# ADC.net
KiCad netlist of a schematic drawn in Altium Designer
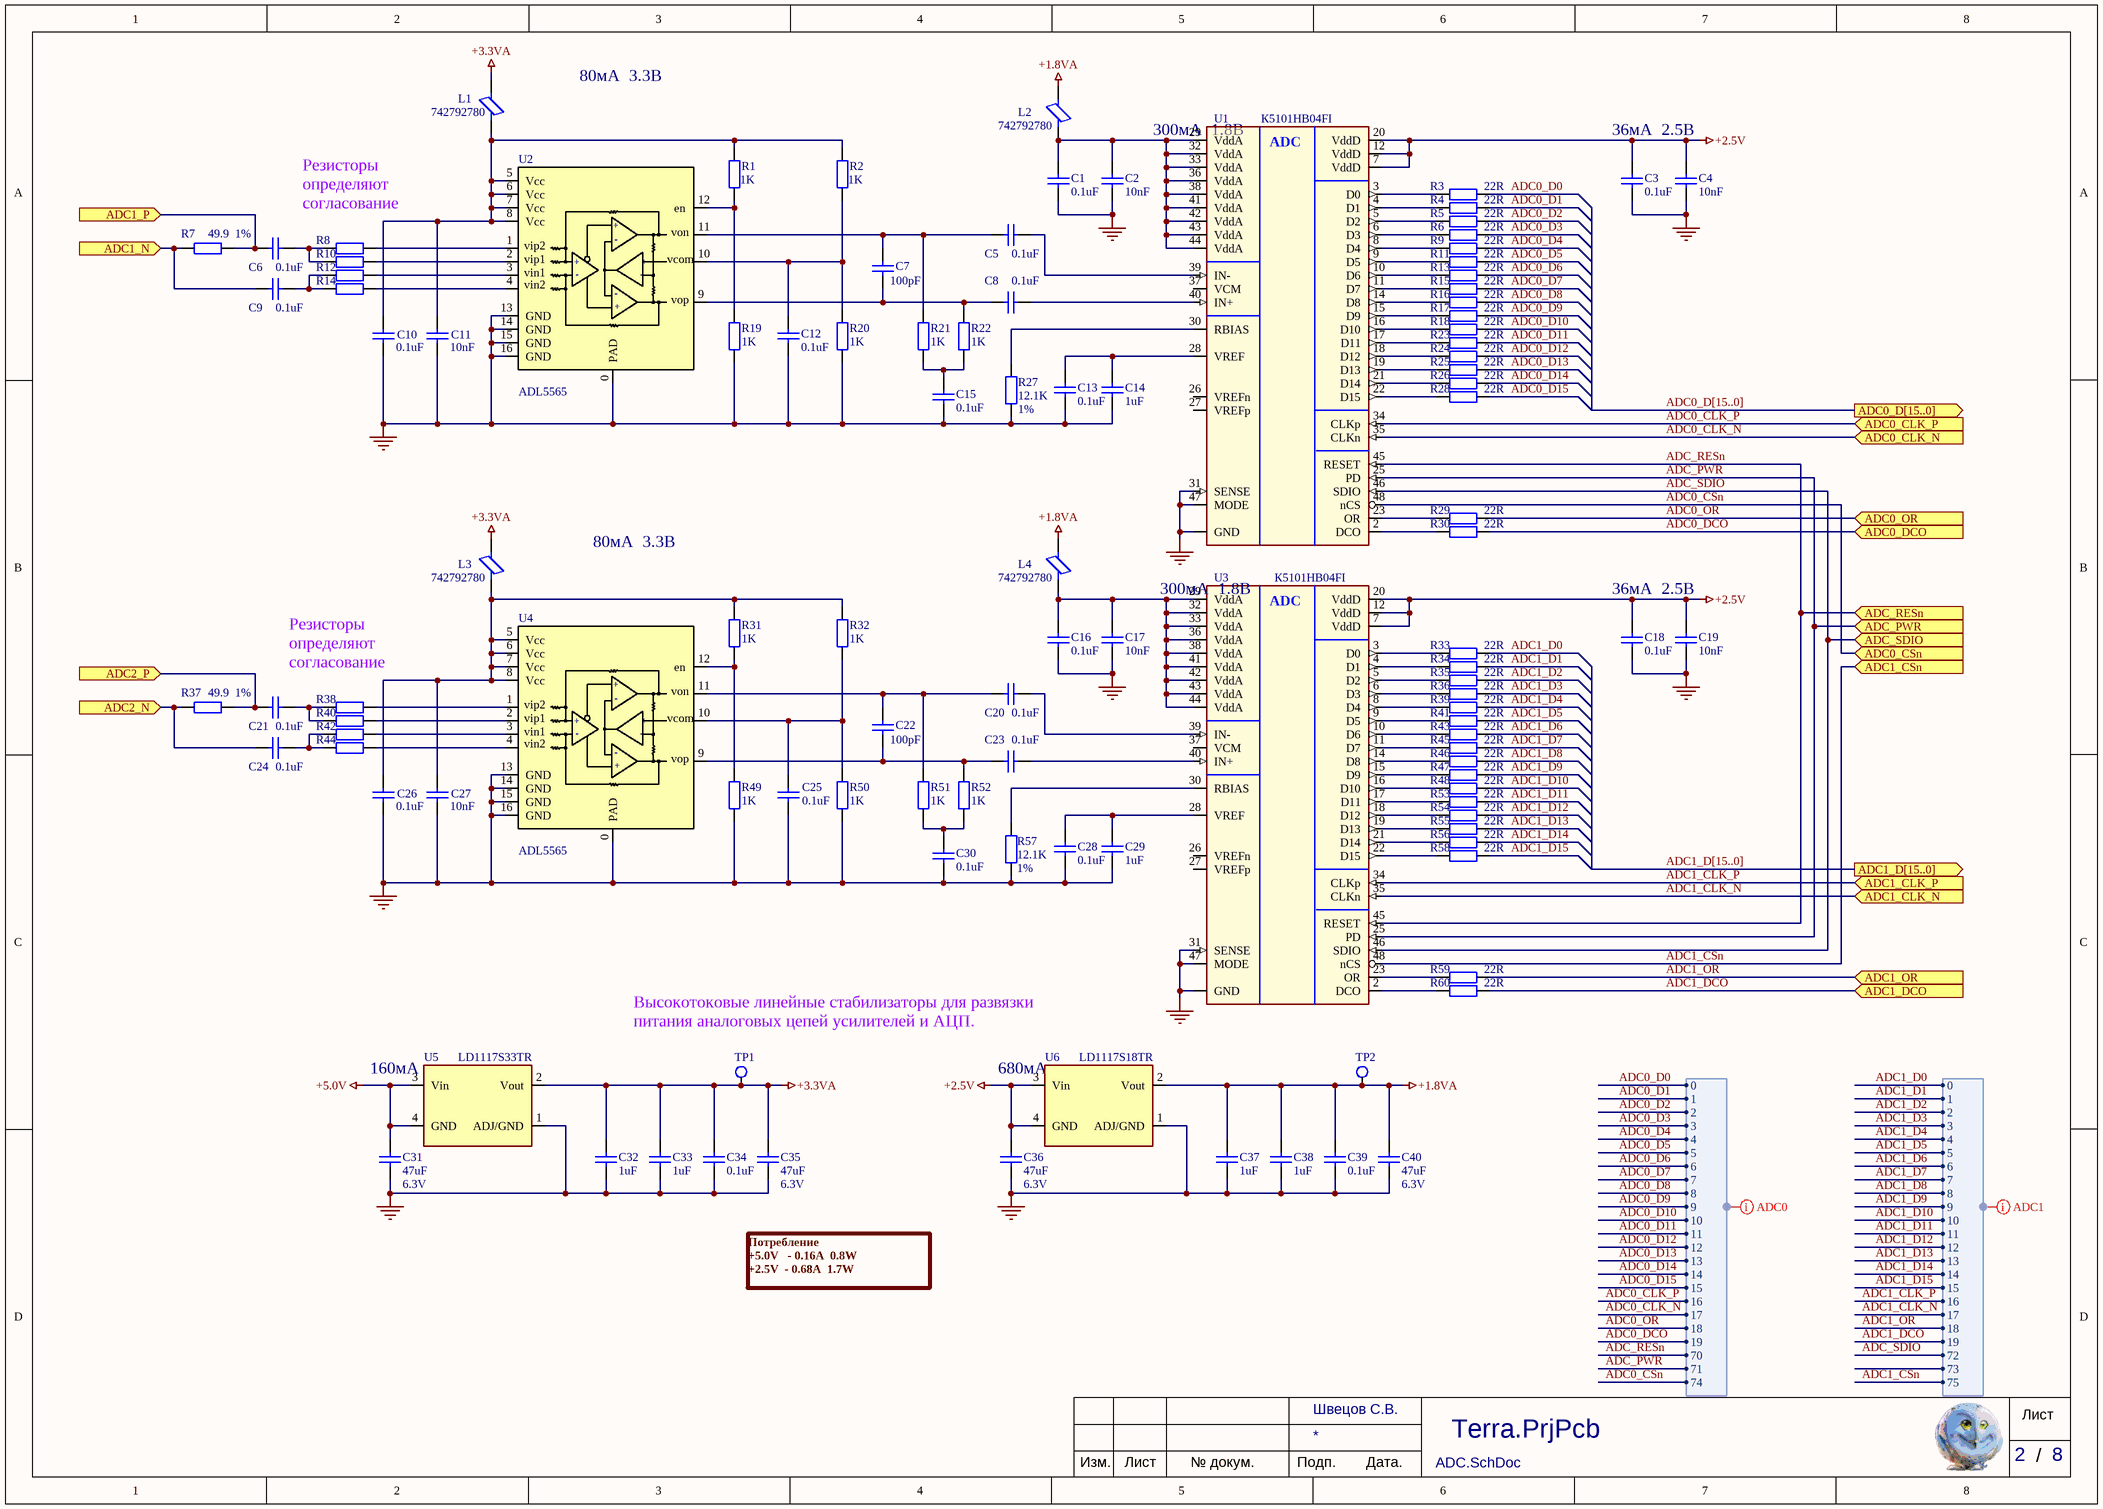
[diagram p0: ADC.SchDoc]

(export (version "E")
  (design (tool "Eeschema 10.0.6"))
  (components
    (comp (ref "C1")
      (value "0.1uF")
      (footprint "C0402")
      (description "Конденсатор керамический")
      (fields (field (name "VOLTAGE") "25V") (field (name "Comment") "Cap"))
      (libsource (lib "Terra") (part "Cap"))
    )
    (comp (ref "C2")
      (value "10nF")
      (footprint "C0402")
      (description "Конденсатор керамический")
      (fields (field (name "VOLTAGE") "25V") (field (name "Comment") "Cap"))
      (libsource (lib "Terra") (part "Cap"))
    )
    (comp (ref "C3")
      (value "0.1uF")
      (footprint "C0402")
      (description "Конденсатор керамический")
      (fields (field (name "VOLTAGE") "25V") (field (name "Comment") "Cap"))
      (libsource (lib "Terra") (part "Cap"))
    )
    (comp (ref "C4")
      (value "10nF")
      (footprint "C0402")
      (description "Конденсатор керамический")
      (fields (field (name "VOLTAGE") "25V") (field (name "Comment") "Cap"))
      (libsource (lib "Terra") (part "Cap"))
    )
    (comp (ref "C5")
      (value "0.1uF")
      (footprint "C0402")
      (description "Конденсатор керамический")
      (fields (field (name "VOLTAGE") "25V") (field (name "Comment") "Cap"))
      (libsource (lib "Terra") (part "Cap"))
    )
    (comp (ref "C6")
      (value "0.1uF")
      (footprint "C0402")
      (description "Конденсатор керамический")
      (fields (field (name "VOLTAGE") "25V") (field (name "Comment") "Cap"))
      (libsource (lib "Terra") (part "Cap"))
    )
    (comp (ref "C7")
      (value "100pF")
      (footprint "C0402")
      (description "Конденсатор керамический")
      (fields (field (name "Comment") "Cap"))
      (libsource (lib "Terra") (part "Cap"))
    )
    (comp (ref "C8")
      (value "0.1uF")
      (footprint "C0402")
      (description "Конденсатор керамический")
      (fields (field (name "VOLTAGE") "25V") (field (name "Comment") "Cap"))
      (libsource (lib "Terra") (part "Cap"))
    )
    (comp (ref "C9")
      (value "0.1uF")
      (footprint "C0402")
      (description "Конденсатор керамический")
      (fields (field (name "VOLTAGE") "25V") (field (name "Comment") "Cap"))
      (libsource (lib "Terra") (part "Cap"))
    )
    (comp (ref "C10")
      (value "0.1uF")
      (footprint "C0402")
      (description "Конденсатор керамический")
      (fields (field (name "VOLTAGE") "25V") (field (name "Comment") "Cap"))
      (libsource (lib "Terra") (part "Cap"))
    )
    (comp (ref "C11")
      (value "10nF")
      (footprint "C0402")
      (description "Конденсатор керамический")
      (fields (field (name "VOLTAGE") "25V") (field (name "Comment") "Cap"))
      (libsource (lib "Terra") (part "Cap"))
    )
    (comp (ref "C12")
      (value "0.1uF")
      (footprint "C0402")
      (description "Конденсатор керамический")
      (fields (field (name "VOLTAGE") "25V") (field (name "Comment") "Cap"))
      (libsource (lib "Terra") (part "Cap"))
    )
    (comp (ref "C13")
      (value "0.1uF")
      (footprint "C0402")
      (description "Конденсатор керамический")
      (fields (field (name "VOLTAGE") "25V") (field (name "Comment") "Cap"))
      (libsource (lib "Terra") (part "Cap"))
    )
    (comp (ref "C14")
      (value "1uF")
      (footprint "C0603")
      (description "Конденсатор керамический")
      (fields (field (name "Comment") "Cap"))
      (libsource (lib "Terra") (part "Cap"))
    )
    (comp (ref "C15")
      (value "0.1uF")
      (footprint "C0402")
      (description "Конденсатор керамический")
      (fields (field (name "VOLTAGE") "25V") (field (name "Comment") "Cap"))
      (libsource (lib "Terra") (part "Cap"))
    )
    (comp (ref "C16")
      (value "0.1uF")
      (footprint "C0402")
      (description "Конденсатор керамический")
      (fields (field (name "VOLTAGE") "25V") (field (name "Comment") "Cap"))
      (libsource (lib "Terra") (part "Cap"))
    )
    (comp (ref "C17")
      (value "10nF")
      (footprint "C0402")
      (description "Конденсатор керамический")
      (fields (field (name "VOLTAGE") "25V") (field (name "Comment") "Cap"))
      (libsource (lib "Terra") (part "Cap"))
    )
    (comp (ref "C18")
      (value "0.1uF")
      (footprint "C0402")
      (description "Конденсатор керамический")
      (fields (field (name "VOLTAGE") "25V") (field (name "Comment") "Cap"))
      (libsource (lib "Terra") (part "Cap"))
    )
    (comp (ref "C19")
      (value "10nF")
      (footprint "C0402")
      (description "Конденсатор керамический")
      (fields (field (name "VOLTAGE") "25V") (field (name "Comment") "Cap"))
      (libsource (lib "Terra") (part "Cap"))
    )
    (comp (ref "C20")
      (value "0.1uF")
      (footprint "C0402")
      (description "Конденсатор керамический")
      (fields (field (name "VOLTAGE") "25V") (field (name "Comment") "Cap"))
      (libsource (lib "Terra") (part "Cap"))
    )
    (comp (ref "C21")
      (value "0.1uF")
      (footprint "C0402")
      (description "Конденсатор керамический")
      (fields (field (name "VOLTAGE") "25V") (field (name "Comment") "Cap"))
      (libsource (lib "Terra") (part "Cap"))
    )
    (comp (ref "C22")
      (value "100pF")
      (footprint "C0402")
      (description "Конденсатор керамический")
      (fields (field (name "Comment") "Cap"))
      (libsource (lib "Terra") (part "Cap"))
    )
    (comp (ref "C23")
      (value "0.1uF")
      (footprint "C0402")
      (description "Конденсатор керамический")
      (fields (field (name "VOLTAGE") "25V") (field (name "Comment") "Cap"))
      (libsource (lib "Terra") (part "Cap"))
    )
    (comp (ref "C24")
      (value "0.1uF")
      (footprint "C0402")
      (description "Конденсатор керамический")
      (fields (field (name "VOLTAGE") "25V") (field (name "Comment") "Cap"))
      (libsource (lib "Terra") (part "Cap"))
    )
    (comp (ref "C25")
      (value "0.1uF")
      (footprint "C0402")
      (description "Конденсатор керамический")
      (fields (field (name "VOLTAGE") "25V") (field (name "Comment") "Cap"))
      (libsource (lib "Terra") (part "Cap"))
    )
    (comp (ref "C26")
      (value "0.1uF")
      (footprint "C0402")
      (description "Конденсатор керамический")
      (fields (field (name "VOLTAGE") "25V") (field (name "Comment") "Cap"))
      (libsource (lib "Terra") (part "Cap"))
    )
    (comp (ref "C27")
      (value "10nF")
      (footprint "C0402")
      (description "Конденсатор керамический")
      (fields (field (name "VOLTAGE") "25V") (field (name "Comment") "Cap"))
      (libsource (lib "Terra") (part "Cap"))
    )
    (comp (ref "C28")
      (value "0.1uF")
      (footprint "C0402")
      (description "Конденсатор керамический")
      (fields (field (name "VOLTAGE") "25V") (field (name "Comment") "Cap"))
      (libsource (lib "Terra") (part "Cap"))
    )
    (comp (ref "C29")
      (value "1uF")
      (footprint "C0603")
      (description "Конденсатор керамический")
      (fields (field (name "Comment") "Cap"))
      (libsource (lib "Terra") (part "Cap"))
    )
    (comp (ref "C30")
      (value "0.1uF")
      (footprint "C0402")
      (description "Конденсатор керамический")
      (fields (field (name "VOLTAGE") "25V") (field (name "Comment") "Cap"))
      (libsource (lib "Terra") (part "Cap"))
    )
    (comp (ref "C31")
      (value "47uF")
      (footprint "C0805")
      (description "C0805C476M9PAC")
      (fields (field (name "VOLTAGE") "6.3V") (field (name "Comment") "Cap"))
      (libsource (lib "Terra") (part "Cap"))
    )
    (comp (ref "C32")
      (value "1uF")
      (footprint "C0603")
      (description "Конденсатор керамический")
      (fields (field (name "Comment") "Cap"))
      (libsource (lib "Terra") (part "Cap"))
    )
    (comp (ref "C33")
      (value "1uF")
      (footprint "C0603")
      (description "Конденсатор керамический")
      (fields (field (name "Comment") "Cap"))
      (libsource (lib "Terra") (part "Cap"))
    )
    (comp (ref "C34")
      (value "0.1uF")
      (footprint "C0402")
      (description "Конденсатор керамический")
      (fields (field (name "VOLTAGE") "25V") (field (name "Comment") "Cap"))
      (libsource (lib "Terra") (part "Cap"))
    )
    (comp (ref "C35")
      (value "47uF")
      (footprint "C0805")
      (description "C0805C476M9PAC")
      (fields (field (name "VOLTAGE") "6.3V") (field (name "Comment") "Cap"))
      (libsource (lib "Terra") (part "Cap"))
    )
    (comp (ref "C36")
      (value "47uF")
      (footprint "C0805")
      (description "C0805C476M9PAC")
      (fields (field (name "VOLTAGE") "6.3V") (field (name "Comment") "Cap"))
      (libsource (lib "Terra") (part "Cap"))
    )
    (comp (ref "C37")
      (value "1uF")
      (footprint "C0603")
      (description "Конденсатор керамический")
      (fields (field (name "Comment") "Cap"))
      (libsource (lib "Terra") (part "Cap"))
    )
    (comp (ref "C38")
      (value "1uF")
      (footprint "C0603")
      (description "Конденсатор керамический")
      (fields (field (name "Comment") "Cap"))
      (libsource (lib "Terra") (part "Cap"))
    )
    (comp (ref "C39")
      (value "0.1uF")
      (footprint "C0402")
      (description "Конденсатор керамический")
      (fields (field (name "VOLTAGE") "25V") (field (name "Comment") "Cap"))
      (libsource (lib "Terra") (part "Cap"))
    )
    (comp (ref "C40")
      (value "47uF")
      (footprint "C0805")
      (description "C0805C476M9PAC")
      (fields (field (name "VOLTAGE") "6.3V") (field (name "Comment") "Cap"))
      (libsource (lib "Terra") (part "Cap"))
    )
    (comp (ref "L1")
      (value "742792780")
      (footprint "L0402")
      (description "Wurth Elektronik EMI FILTERS FERRITE BEAD, 220R@100MHz, 0.35R")
      (libsource (lib "Terra") (part "BEAD_FERRITE_SM"))
    )
    (comp (ref "L2")
      (value "742792780")
      (footprint "L0402")
      (description "Wurth Elektronik EMI FILTERS FERRITE BEAD, 220R@100MHz, 0.35R")
      (libsource (lib "Terra") (part "BEAD_FERRITE_SM"))
    )
    (comp (ref "L3")
      (value "742792780")
      (footprint "L0402")
      (description "Wurth Elektronik EMI FILTERS FERRITE BEAD, 220R@100MHz, 0.35R")
      (libsource (lib "Terra") (part "BEAD_FERRITE_SM"))
    )
    (comp (ref "L4")
      (value "742792780")
      (footprint "L0402")
      (description "Wurth Elektronik EMI FILTERS FERRITE BEAD, 220R@100MHz, 0.35R")
      (libsource (lib "Terra") (part "BEAD_FERRITE_SM"))
    )
    (comp (ref "R1")
      (value "1K")
      (footprint "R0402")
      (description "Резистор")
      (fields (field (name "Comment") "Res2"))
      (libsource (lib "") (part "Res2_1"))
    )
    (comp (ref "R2")
      (value "1K")
      (footprint "R0402")
      (description "Резистор")
      (fields (field (name "Comment") "Res2"))
      (libsource (lib "") (part "Res2_1"))
    )
    (comp (ref "R3")
      (value "22R")
      (footprint "R0402")
      (description "Резистор")
      (fields (field (name "Comment") "Res2"))
      (libsource (lib "Terra") (part "Res2"))
    )
    (comp (ref "R4")
      (value "22R")
      (footprint "R0402")
      (description "Резистор")
      (fields (field (name "Comment") "Res2"))
      (libsource (lib "Terra") (part "Res2"))
    )
    (comp (ref "R5")
      (value "22R")
      (footprint "R0402")
      (description "Резистор")
      (fields (field (name "Comment") "Res2"))
      (libsource (lib "Terra") (part "Res2"))
    )
    (comp (ref "R6")
      (value "22R")
      (footprint "R0402")
      (description "Резистор")
      (fields (field (name "Comment") "Res2"))
      (libsource (lib "Terra") (part "Res2"))
    )
    (comp (ref "R7")
      (value "49.9")
      (footprint "R0402")
      (description "Резистор")
      (fields (field (name "PRECISION") "1%") (field (name "Comment") "Res2"))
      (libsource (lib "") (part "Res2_2"))
    )
    (comp (ref "R8")
      (value "Res2")
      (footprint "R0402")
      (description "Резистор")
      (libsource (lib "Terra") (part "Res2"))
    )
    (comp (ref "R9")
      (value "22R")
      (footprint "R0402")
      (description "Резистор")
      (fields (field (name "Comment") "Res2"))
      (libsource (lib "Terra") (part "Res2"))
    )
    (comp (ref "R10")
      (value "Res2")
      (footprint "R0402")
      (description "Резистор")
      (libsource (lib "Terra") (part "Res2"))
    )
    (comp (ref "R11")
      (value "22R")
      (footprint "R0402")
      (description "Резистор")
      (fields (field (name "Comment") "Res2"))
      (libsource (lib "Terra") (part "Res2"))
    )
    (comp (ref "R12")
      (value "Res2")
      (footprint "R0402")
      (description "Резистор")
      (libsource (lib "Terra") (part "Res2"))
    )
    (comp (ref "R13")
      (value "22R")
      (footprint "R0402")
      (description "Резистор")
      (fields (field (name "Comment") "Res2"))
      (libsource (lib "Terra") (part "Res2"))
    )
    (comp (ref "R14")
      (value "Res2")
      (footprint "R0402")
      (description "Резистор")
      (libsource (lib "Terra") (part "Res2"))
    )
    (comp (ref "R15")
      (value "22R")
      (footprint "R0402")
      (description "Резистор")
      (fields (field (name "Comment") "Res2"))
      (libsource (lib "Terra") (part "Res2"))
    )
    (comp (ref "R16")
      (value "22R")
      (footprint "R0402")
      (description "Резистор")
      (fields (field (name "Comment") "Res2"))
      (libsource (lib "Terra") (part "Res2"))
    )
    (comp (ref "R17")
      (value "22R")
      (footprint "R0402")
      (description "Резистор")
      (fields (field (name "Comment") "Res2"))
      (libsource (lib "Terra") (part "Res2"))
    )
    (comp (ref "R18")
      (value "22R")
      (footprint "R0402")
      (description "Резистор")
      (fields (field (name "Comment") "Res2"))
      (libsource (lib "Terra") (part "Res2"))
    )
    (comp (ref "R19")
      (value "1K")
      (footprint "R0402")
      (description "Резистор")
      (fields (field (name "Comment") "Res2"))
      (libsource (lib "") (part "Res2_1"))
    )
    (comp (ref "R20")
      (value "1K")
      (footprint "R0402")
      (description "Резистор")
      (fields (field (name "Comment") "Res2"))
      (libsource (lib "") (part "Res2_1"))
    )
    (comp (ref "R21")
      (value "1K")
      (footprint "R0402")
      (description "Резистор")
      (fields (field (name "Comment") "Res2"))
      (libsource (lib "") (part "Res2_1"))
    )
    (comp (ref "R22")
      (value "1K")
      (footprint "R0402")
      (description "Резистор")
      (fields (field (name "Comment") "Res2"))
      (libsource (lib "") (part "Res2_1"))
    )
    (comp (ref "R23")
      (value "22R")
      (footprint "R0402")
      (description "Резистор")
      (fields (field (name "Comment") "Res2"))
      (libsource (lib "Terra") (part "Res2"))
    )
    (comp (ref "R24")
      (value "22R")
      (footprint "R0402")
      (description "Резистор")
      (fields (field (name "Comment") "Res2"))
      (libsource (lib "Terra") (part "Res2"))
    )
    (comp (ref "R25")
      (value "22R")
      (footprint "R0402")
      (description "Резистор")
      (fields (field (name "Comment") "Res2"))
      (libsource (lib "Terra") (part "Res2"))
    )
    (comp (ref "R26")
      (value "22R")
      (footprint "R0402")
      (description "Резистор")
      (fields (field (name "Comment") "Res2"))
      (libsource (lib "Terra") (part "Res2"))
    )
    (comp (ref "R27")
      (value "12.1K")
      (footprint "R0402")
      (description "Резистор")
      (fields (field (name "PRECISION") "1%") (field (name "Comment") "Res2"))
      (libsource (lib "") (part "Res2_1"))
    )
    (comp (ref "R28")
      (value "22R")
      (footprint "R0402")
      (description "Резистор")
      (fields (field (name "Comment") "Res2"))
      (libsource (lib "Terra") (part "Res2"))
    )
    (comp (ref "R29")
      (value "22R")
      (footprint "R0402")
      (description "Резистор")
      (fields (field (name "Comment") "Res2"))
      (libsource (lib "Terra") (part "Res2"))
    )
    (comp (ref "R30")
      (value "22R")
      (footprint "R0402")
      (description "Резистор")
      (fields (field (name "Comment") "Res2"))
      (libsource (lib "Terra") (part "Res2"))
    )
    (comp (ref "R31")
      (value "1K")
      (footprint "R0402")
      (description "Резистор")
      (fields (field (name "Comment") "Res2"))
      (libsource (lib "") (part "Res2_1"))
    )
    (comp (ref "R32")
      (value "1K")
      (footprint "R0402")
      (description "Резистор")
      (fields (field (name "Comment") "Res2"))
      (libsource (lib "") (part "Res2_1"))
    )
    (comp (ref "R33")
      (value "22R")
      (footprint "R0402")
      (description "Резистор")
      (fields (field (name "Comment") "Res2"))
      (libsource (lib "Terra") (part "Res2"))
    )
    (comp (ref "R34")
      (value "22R")
      (footprint "R0402")
      (description "Резистор")
      (fields (field (name "Comment") "Res2"))
      (libsource (lib "Terra") (part "Res2"))
    )
    (comp (ref "R35")
      (value "22R")
      (footprint "R0402")
      (description "Резистор")
      (fields (field (name "Comment") "Res2"))
      (libsource (lib "Terra") (part "Res2"))
    )
    (comp (ref "R36")
      (value "22R")
      (footprint "R0402")
      (description "Резистор")
      (fields (field (name "Comment") "Res2"))
      (libsource (lib "Terra") (part "Res2"))
    )
    (comp (ref "R37")
      (value "49.9")
      (footprint "R0402")
      (description "Резистор")
      (fields (field (name "PRECISION") "1%") (field (name "Comment") "Res2"))
      (libsource (lib "") (part "Res2_2"))
    )
    (comp (ref "R38")
      (value "Res2")
      (footprint "R0402")
      (description "Резистор")
      (libsource (lib "Terra") (part "Res2"))
    )
    (comp (ref "R39")
      (value "22R")
      (footprint "R0402")
      (description "Резистор")
      (fields (field (name "Comment") "Res2"))
      (libsource (lib "Terra") (part "Res2"))
    )
    (comp (ref "R40")
      (value "Res2")
      (footprint "R0402")
      (description "Резистор")
      (libsource (lib "Terra") (part "Res2"))
    )
    (comp (ref "R41")
      (value "22R")
      (footprint "R0402")
      (description "Резистор")
      (fields (field (name "Comment") "Res2"))
      (libsource (lib "Terra") (part "Res2"))
    )
    (comp (ref "R42")
      (value "Res2")
      (footprint "R0402")
      (description "Резистор")
      (libsource (lib "Terra") (part "Res2"))
    )
    (comp (ref "R43")
      (value "22R")
      (footprint "R0402")
      (description "Резистор")
      (fields (field (name "Comment") "Res2"))
      (libsource (lib "Terra") (part "Res2"))
    )
    (comp (ref "R44")
      (value "Res2")
      (footprint "R0402")
      (description "Резистор")
      (libsource (lib "Terra") (part "Res2"))
    )
    (comp (ref "R45")
      (value "22R")
      (footprint "R0402")
      (description "Резистор")
      (fields (field (name "Comment") "Res2"))
      (libsource (lib "Terra") (part "Res2"))
    )
    (comp (ref "R46")
      (value "22R")
      (footprint "R0402")
      (description "Резистор")
      (fields (field (name "Comment") "Res2"))
      (libsource (lib "Terra") (part "Res2"))
    )
    (comp (ref "R47")
      (value "22R")
      (footprint "R0402")
      (description "Резистор")
      (fields (field (name "Comment") "Res2"))
      (libsource (lib "Terra") (part "Res2"))
    )
    (comp (ref "R48")
      (value "22R")
      (footprint "R0402")
      (description "Резистор")
      (fields (field (name "Comment") "Res2"))
      (libsource (lib "Terra") (part "Res2"))
    )
    (comp (ref "R49")
      (value "1K")
      (footprint "R0402")
      (description "Резистор")
      (fields (field (name "Comment") "Res2"))
      (libsource (lib "") (part "Res2_1"))
    )
    (comp (ref "R50")
      (value "1K")
      (footprint "R0402")
      (description "Резистор")
      (fields (field (name "Comment") "Res2"))
      (libsource (lib "") (part "Res2_1"))
    )
    (comp (ref "R51")
      (value "1K")
      (footprint "R0402")
      (description "Резистор")
      (fields (field (name "Comment") "Res2"))
      (libsource (lib "") (part "Res2_1"))
    )
    (comp (ref "R52")
      (value "1K")
      (footprint "R0402")
      (description "Резистор")
      (fields (field (name "Comment") "Res2"))
      (libsource (lib "") (part "Res2_1"))
    )
    (comp (ref "R53")
      (value "22R")
      (footprint "R0402")
      (description "Резистор")
      (fields (field (name "Comment") "Res2"))
      (libsource (lib "Terra") (part "Res2"))
    )
    (comp (ref "R54")
      (value "22R")
      (footprint "R0402")
      (description "Резистор")
      (fields (field (name "Comment") "Res2"))
      (libsource (lib "Terra") (part "Res2"))
    )
    (comp (ref "R55")
      (value "22R")
      (footprint "R0402")
      (description "Резистор")
      (fields (field (name "Comment") "Res2"))
      (libsource (lib "Terra") (part "Res2"))
    )
    (comp (ref "R56")
      (value "22R")
      (footprint "R0402")
      (description "Резистор")
      (fields (field (name "Comment") "Res2"))
      (libsource (lib "Terra") (part "Res2"))
    )
    (comp (ref "R57")
      (value "12.1K")
      (footprint "R0402")
      (description "Резистор")
      (fields (field (name "PRECISION") "1%") (field (name "Comment") "Res2"))
      (libsource (lib "") (part "Res2_1"))
    )
    (comp (ref "R58")
      (value "22R")
      (footprint "R0402")
      (description "Резистор")
      (fields (field (name "Comment") "Res2"))
      (libsource (lib "Terra") (part "Res2"))
    )
    (comp (ref "R59")
      (value "22R")
      (footprint "R0402")
      (description "Резистор")
      (fields (field (name "Comment") "Res2"))
      (libsource (lib "Terra") (part "Res2"))
    )
    (comp (ref "R60")
      (value "22R")
      (footprint "R0402")
      (description "Резистор")
      (fields (field (name "Comment") "Res2"))
      (libsource (lib "Terra") (part "Res2"))
    )
    (comp (ref "TP1")
      (value "~")
      (footprint "TP_0MM5_1MM0")
      (description "Тестовая точка на плате")
      (libsource (lib "*") (part "Test_Point"))
    )
    (comp (ref "TP2")
      (value "~")
      (footprint "TP_0MM5_1MM0")
      (description "Тестовая точка на плате")
      (libsource (lib "*") (part "Test_Point"))
    )
    (comp (ref "U1")
      (value "К5101НВ04FI")
      (footprint "VQFN48L")
      (description "АЦП 95мГц 14бит")
      (libsource (lib "Terra") (part "К5101НВ04FI"))
    )
    (comp (ref "U2")
      (value "ADL5565")
      (footprint "CP_16_2_ADI-L")
      (description "6 GHz Differential Amplifier")
      (libsource (lib "Terra") (part "ADL5565"))
    )
    (comp (ref "U3")
      (value "К5101НВ04FI")
      (footprint "VQFN48L")
      (description "АЦП 95мГц 14бит")
      (libsource (lib "Terra") (part "К5101НВ04FI"))
    )
    (comp (ref "U4")
      (value "ADL5565")
      (footprint "CP_16_2_ADI-L")
      (description "6 GHz Differential Amplifier")
      (libsource (lib "Terra") (part "ADL5565"))
    )
    (comp (ref "U5")
      (value "LD1117S33TR")
      (footprint "SOT223")
      (description "Линейный стабилизатор +3.3V")
      (fields (field (name "Comment") "LD1117S12TR"))
      (libsource (lib "Terra") (part "LD1117S12TR"))
    )
    (comp (ref "U6")
      (value "LD1117S18TR")
      (footprint "SOT223")
      (description "Линейный стабилизатор 1.8V")
      (fields (field (name "Comment") "LD1117S12TR"))
      (libsource (lib "Terra") (part "LD1117S12TR"))
    )
  )
  (nets
    (net (code "1") (name "+1.8VA") (class "Default")
      (node (ref "C37") (pin "1") (pinfunction "1_1") (pintype "passive"))
      (node (ref "C38") (pin "1") (pinfunction "1_1") (pintype "passive"))
      (node (ref "C39") (pin "1") (pinfunction "1_1") (pintype "passive"))
      (node (ref "C40") (pin "1") (pinfunction "1_1") (pintype "passive"))
      (node (ref "L2") (pin "1") (pinfunction "1_1") (pintype "passive"))
      (node (ref "L4") (pin "1") (pinfunction "1_1") (pintype "passive"))
      (node (ref "TP2") (pin "1") (pinfunction "e1_1") (pintype "passive"))
      (node (ref "U6") (pin "2") (pinfunction "Vout_2") (pintype "passive"))
    )
    (net (code "2") (name "+2.5V") (class "Default")
      (node (ref "C18") (pin "1") (pinfunction "1_1") (pintype "passive"))
      (node (ref "C19") (pin "1") (pinfunction "1_1") (pintype "passive"))
      (node (ref "C3") (pin "1") (pinfunction "1_1") (pintype "passive"))
      (node (ref "C36") (pin "1") (pinfunction "1_1") (pintype "passive"))
      (node (ref "C4") (pin "1") (pinfunction "1_1") (pintype "passive"))
      (node (ref "U1") (pin "12") (pinfunction "VddD_12") (pintype "power_in"))
      (node (ref "U1") (pin "20") (pinfunction "VddD_20") (pintype "power_in"))
      (node (ref "U1") (pin "7") (pinfunction "VddD_7") (pintype "power_in"))
      (node (ref "U3") (pin "12") (pinfunction "VddD_12") (pintype "power_in"))
      (node (ref "U3") (pin "20") (pinfunction "VddD_20") (pintype "power_in"))
      (node (ref "U3") (pin "7") (pinfunction "VddD_7") (pintype "power_in"))
      (node (ref "U6") (pin "3") (pinfunction "Vin_3") (pintype "passive"))
      (node (ref "U6") (pin "4") (pinfunction "GND_4") (pintype "passive"))
    )
    (net (code "3") (name "+3.3VA") (class "Default")
      (node (ref "C32") (pin "1") (pinfunction "1_1") (pintype "passive"))
      (node (ref "C33") (pin "1") (pinfunction "1_1") (pintype "passive"))
      (node (ref "C34") (pin "1") (pinfunction "1_1") (pintype "passive"))
      (node (ref "C35") (pin "1") (pinfunction "1_1") (pintype "passive"))
      (node (ref "L1") (pin "1") (pinfunction "1_1") (pintype "passive"))
      (node (ref "L3") (pin "1") (pinfunction "1_1") (pintype "passive"))
      (node (ref "TP1") (pin "1") (pinfunction "e1_1") (pintype "passive"))
      (node (ref "U5") (pin "2") (pinfunction "Vout_2") (pintype "passive"))
    )
    (net (code "4") (name "+5.0V") (class "Default")
      (node (ref "C31") (pin "1") (pinfunction "1_1") (pintype "passive"))
      (node (ref "U5") (pin "3") (pinfunction "Vin_3") (pintype "passive"))
      (node (ref "U5") (pin "4") (pinfunction "GND_4") (pintype "passive"))
    )
    (net (code "5") (name "/ADC0_CLK_N") (class "Default")
      (node (ref "U1") (pin "35") (pinfunction "CLKn_35") (pintype "input"))
    )
    (net (code "6") (name "/ADC0_CLK_P") (class "Default")
      (node (ref "U1") (pin "34") (pinfunction "CLKp_34") (pintype "input"))
    )
    (net (code "7") (name "/ADC0_CSn") (class "Default")
      (node (ref "U1") (pin "48") (pinfunction "nCS_48") (pintype "passive"))
    )
    (net (code "8") (name "/ADC0_D0") (class "Default")
      (node (ref "R3") (pin "2") (pinfunction "2_2") (pintype "passive"))
    )
    (net (code "9") (name "/ADC0_D1") (class "Default")
      (node (ref "R4") (pin "2") (pinfunction "2_2") (pintype "passive"))
    )
    (net (code "10") (name "/ADC0_D2") (class "Default")
      (node (ref "R5") (pin "2") (pinfunction "2_2") (pintype "passive"))
    )
    (net (code "11") (name "/ADC0_D3") (class "Default")
      (node (ref "R6") (pin "2") (pinfunction "2_2") (pintype "passive"))
    )
    (net (code "12") (name "/ADC0_D4") (class "Default")
      (node (ref "R9") (pin "2") (pinfunction "2_2") (pintype "passive"))
    )
    (net (code "13") (name "/ADC0_D5") (class "Default")
      (node (ref "R11") (pin "2") (pinfunction "2_2") (pintype "passive"))
    )
    (net (code "14") (name "/ADC0_D6") (class "Default")
      (node (ref "R13") (pin "2") (pinfunction "2_2") (pintype "passive"))
    )
    (net (code "15") (name "/ADC0_D7") (class "Default")
      (node (ref "R15") (pin "2") (pinfunction "2_2") (pintype "passive"))
    )
    (net (code "16") (name "/ADC0_D8") (class "Default")
      (node (ref "R16") (pin "2") (pinfunction "2_2") (pintype "passive"))
    )
    (net (code "17") (name "/ADC0_D9") (class "Default")
      (node (ref "R17") (pin "2") (pinfunction "2_2") (pintype "passive"))
    )
    (net (code "18") (name "/ADC0_D10") (class "Default")
      (node (ref "R18") (pin "2") (pinfunction "2_2") (pintype "passive"))
    )
    (net (code "19") (name "/ADC0_D11") (class "Default")
      (node (ref "R23") (pin "2") (pinfunction "2_2") (pintype "passive"))
    )
    (net (code "20") (name "/ADC0_D12") (class "Default")
      (node (ref "R24") (pin "2") (pinfunction "2_2") (pintype "passive"))
    )
    (net (code "21") (name "/ADC0_D13") (class "Default")
      (node (ref "R25") (pin "2") (pinfunction "2_2") (pintype "passive"))
    )
    (net (code "22") (name "/ADC0_D14") (class "Default")
      (node (ref "R26") (pin "2") (pinfunction "2_2") (pintype "passive"))
    )
    (net (code "23") (name "/ADC0_D15") (class "Default")
      (node (ref "R28") (pin "2") (pinfunction "2_2") (pintype "passive"))
    )
    (net (code "24") (name "/ADC0_DCO") (class "Default")
      (node (ref "R30") (pin "2") (pinfunction "2_2") (pintype "passive"))
    )
    (net (code "26") (name "/ADC0_OR") (class "Default")
      (node (ref "R29") (pin "2") (pinfunction "2_2") (pintype "passive"))
    )
    (net (code "27") (name "/ADC1_CLK_N") (class "Default")
      (node (ref "U3") (pin "35") (pinfunction "CLKn_35") (pintype "input"))
    )
    (net (code "28") (name "/ADC1_CLK_P") (class "Default")
      (node (ref "U3") (pin "34") (pinfunction "CLKp_34") (pintype "input"))
    )
    (net (code "29") (name "/ADC1_CSn") (class "Default")
      (node (ref "U3") (pin "48") (pinfunction "nCS_48") (pintype "passive"))
    )
    (net (code "30") (name "/ADC1_D0") (class "Default")
      (node (ref "R33") (pin "2") (pinfunction "2_2") (pintype "passive"))
    )
    (net (code "31") (name "/ADC1_D1") (class "Default")
      (node (ref "R34") (pin "2") (pinfunction "2_2") (pintype "passive"))
    )
    (net (code "32") (name "/ADC1_D2") (class "Default")
      (node (ref "R35") (pin "2") (pinfunction "2_2") (pintype "passive"))
    )
    (net (code "33") (name "/ADC1_D3") (class "Default")
      (node (ref "R36") (pin "2") (pinfunction "2_2") (pintype "passive"))
    )
    (net (code "34") (name "/ADC1_D4") (class "Default")
      (node (ref "R39") (pin "2") (pinfunction "2_2") (pintype "passive"))
    )
    (net (code "35") (name "/ADC1_D5") (class "Default")
      (node (ref "R41") (pin "2") (pinfunction "2_2") (pintype "passive"))
    )
    (net (code "36") (name "/ADC1_D6") (class "Default")
      (node (ref "R43") (pin "2") (pinfunction "2_2") (pintype "passive"))
    )
    (net (code "37") (name "/ADC1_D7") (class "Default")
      (node (ref "R45") (pin "2") (pinfunction "2_2") (pintype "passive"))
    )
    (net (code "38") (name "/ADC1_D8") (class "Default")
      (node (ref "R46") (pin "2") (pinfunction "2_2") (pintype "passive"))
    )
    (net (code "39") (name "/ADC1_D9") (class "Default")
      (node (ref "R47") (pin "2") (pinfunction "2_2") (pintype "passive"))
    )
    (net (code "40") (name "/ADC1_D10") (class "Default")
      (node (ref "R48") (pin "2") (pinfunction "2_2") (pintype "passive"))
    )
    (net (code "41") (name "/ADC1_D11") (class "Default")
      (node (ref "R53") (pin "2") (pinfunction "2_2") (pintype "passive"))
    )
    (net (code "42") (name "/ADC1_D12") (class "Default")
      (node (ref "R54") (pin "2") (pinfunction "2_2") (pintype "passive"))
    )
    (net (code "43") (name "/ADC1_D13") (class "Default")
      (node (ref "R55") (pin "2") (pinfunction "2_2") (pintype "passive"))
    )
    (net (code "44") (name "/ADC1_D14") (class "Default")
      (node (ref "R56") (pin "2") (pinfunction "2_2") (pintype "passive"))
    )
    (net (code "45") (name "/ADC1_D15") (class "Default")
      (node (ref "R58") (pin "2") (pinfunction "2_2") (pintype "passive"))
    )
    (net (code "46") (name "/ADC1_DCO") (class "Default")
      (node (ref "R60") (pin "2") (pinfunction "2_2") (pintype "passive"))
    )
    (net (code "48") (name "/ADC1_N") (class "Default")
      (node (ref "C9") (pin "2") (pinfunction "2_2") (pintype "passive"))
      (node (ref "R7") (pin "1") (pinfunction "1_1") (pintype "passive"))
    )
    (net (code "49") (name "/ADC1_OR") (class "Default")
      (node (ref "R59") (pin "2") (pinfunction "2_2") (pintype "passive"))
    )
    (net (code "50") (name "/ADC1_P") (class "Default")
      (node (ref "C6") (pin "2") (pinfunction "2_2") (pintype "passive"))
      (node (ref "R7") (pin "2") (pinfunction "2_2") (pintype "passive"))
    )
    (net (code "51") (name "/ADC2_N") (class "Default")
      (node (ref "C24") (pin "2") (pinfunction "2_2") (pintype "passive"))
      (node (ref "R37") (pin "1") (pinfunction "1_1") (pintype "passive"))
    )
    (net (code "52") (name "/ADC2_P") (class "Default")
      (node (ref "C21") (pin "2") (pinfunction "2_2") (pintype "passive"))
      (node (ref "R37") (pin "2") (pinfunction "2_2") (pintype "passive"))
    )
    (net (code "53") (name "/ADC_PWR") (class "Default")
      (node (ref "U1") (pin "25") (pinfunction "PD_25") (pintype "input"))
      (node (ref "U3") (pin "25") (pinfunction "PD_25") (pintype "input"))
    )
    (net (code "54") (name "/ADC_RESn") (class "Default")
      (node (ref "U1") (pin "45") (pinfunction "RESET_45") (pintype "input"))
      (node (ref "U3") (pin "45") (pinfunction "RESET_45") (pintype "input"))
    )
    (net (code "55") (name "/ADC_SDIO") (class "Default")
      (node (ref "U1") (pin "46") (pinfunction "SDIO_46") (pintype "input"))
      (node (ref "U3") (pin "46") (pinfunction "SDIO_46") (pintype "input"))
    )
    (net (code "56") (name "GND") (class "Default")
      (node (ref "C1") (pin "2") (pinfunction "2_2") (pintype "passive"))
      (node (ref "C10") (pin "2") (pinfunction "2_2") (pintype "passive"))
      (node (ref "C11") (pin "2") (pinfunction "2_2") (pintype "passive"))
      (node (ref "C12") (pin "2") (pinfunction "2_2") (pintype "passive"))
      (node (ref "C13") (pin "2") (pinfunction "2_2") (pintype "passive"))
      (node (ref "C14") (pin "2") (pinfunction "2_2") (pintype "passive"))
      (node (ref "C15") (pin "2") (pinfunction "2_2") (pintype "passive"))
      (node (ref "C16") (pin "2") (pinfunction "2_2") (pintype "passive"))
      (node (ref "C17") (pin "2") (pinfunction "2_2") (pintype "passive"))
      (node (ref "C18") (pin "2") (pinfunction "2_2") (pintype "passive"))
      (node (ref "C19") (pin "2") (pinfunction "2_2") (pintype "passive"))
      (node (ref "C2") (pin "2") (pinfunction "2_2") (pintype "passive"))
      (node (ref "C25") (pin "2") (pinfunction "2_2") (pintype "passive"))
      (node (ref "C26") (pin "2") (pinfunction "2_2") (pintype "passive"))
      (node (ref "C27") (pin "2") (pinfunction "2_2") (pintype "passive"))
      (node (ref "C28") (pin "2") (pinfunction "2_2") (pintype "passive"))
      (node (ref "C29") (pin "2") (pinfunction "2_2") (pintype "passive"))
      (node (ref "C3") (pin "2") (pinfunction "2_2") (pintype "passive"))
      (node (ref "C30") (pin "2") (pinfunction "2_2") (pintype "passive"))
      (node (ref "C31") (pin "2") (pinfunction "2_2") (pintype "passive"))
      (node (ref "C32") (pin "2") (pinfunction "2_2") (pintype "passive"))
      (node (ref "C33") (pin "2") (pinfunction "2_2") (pintype "passive"))
      (node (ref "C34") (pin "2") (pinfunction "2_2") (pintype "passive"))
      (node (ref "C35") (pin "2") (pinfunction "2_2") (pintype "passive"))
      (node (ref "C36") (pin "2") (pinfunction "2_2") (pintype "passive"))
      (node (ref "C37") (pin "2") (pinfunction "2_2") (pintype "passive"))
      (node (ref "C38") (pin "2") (pinfunction "2_2") (pintype "passive"))
      (node (ref "C39") (pin "2") (pinfunction "2_2") (pintype "passive"))
      (node (ref "C4") (pin "2") (pinfunction "2_2") (pintype "passive"))
      (node (ref "C40") (pin "2") (pinfunction "2_2") (pintype "passive"))
      (node (ref "R19") (pin "2") (pinfunction "2_2") (pintype "passive"))
      (node (ref "R20") (pin "2") (pinfunction "2_2") (pintype "passive"))
      (node (ref "R27") (pin "2") (pinfunction "2_2") (pintype "passive"))
      (node (ref "R49") (pin "2") (pinfunction "2_2") (pintype "passive"))
      (node (ref "R50") (pin "2") (pinfunction "2_2") (pintype "passive"))
      (node (ref "R57") (pin "2") (pinfunction "2_2") (pintype "passive"))
      (node (ref "U1") (pin "0") (pinfunction "GND_0") (pintype "power_in"))
      (node (ref "U1") (pin "31") (pinfunction "SENSE_31") (pintype "input"))
      (node (ref "U1") (pin "47") (pinfunction "MODE_47") (pintype "passive"))
      (node (ref "U2") (pin "0") (pinfunction "PAD_0") (pintype "power_in"))
      (node (ref "U2") (pin "13") (pinfunction "GND_13") (pintype "power_in"))
      (node (ref "U2") (pin "14") (pinfunction "GND_14") (pintype "power_in"))
      (node (ref "U2") (pin "15") (pinfunction "GND_15") (pintype "power_in"))
      (node (ref "U2") (pin "16") (pinfunction "GND_16") (pintype "power_in"))
      (node (ref "U3") (pin "0") (pinfunction "GND_0") (pintype "power_in"))
      (node (ref "U3") (pin "31") (pinfunction "SENSE_31") (pintype "input"))
      (node (ref "U3") (pin "47") (pinfunction "MODE_47") (pintype "passive"))
      (node (ref "U4") (pin "0") (pinfunction "PAD_0") (pintype "power_in"))
      (node (ref "U4") (pin "13") (pinfunction "GND_13") (pintype "power_in"))
      (node (ref "U4") (pin "14") (pinfunction "GND_14") (pintype "power_in"))
      (node (ref "U4") (pin "15") (pinfunction "GND_15") (pintype "power_in"))
      (node (ref "U4") (pin "16") (pinfunction "GND_16") (pintype "power_in"))
      (node (ref "U5") (pin "1") (pinfunction "ADJ/GND_1") (pintype "passive"))
      (node (ref "U6") (pin "1") (pinfunction "ADJ/GND_1") (pintype "passive"))
    )
    (net (code "57") (name "Net-(C1-Pad1)") (class "Default")
      (node (ref "C1") (pin "1") (pinfunction "1_1") (pintype "passive"))
      (node (ref "C2") (pin "1") (pinfunction "1_1") (pintype "passive"))
      (node (ref "L2") (pin "2") (pinfunction "2_2") (pintype "passive"))
      (node (ref "U1") (pin "29") (pinfunction "VddA_29") (pintype "power_in"))
      (node (ref "U1") (pin "32") (pinfunction "VddA_32") (pintype "power_in"))
      (node (ref "U1") (pin "33") (pinfunction "VddA_33") (pintype "power_in"))
      (node (ref "U1") (pin "36") (pinfunction "VddA_36") (pintype "power_in"))
      (node (ref "U1") (pin "38") (pinfunction "VddA_38") (pintype "power_in"))
      (node (ref "U1") (pin "41") (pinfunction "VddA_41") (pintype "power_in"))
      (node (ref "U1") (pin "42") (pinfunction "VddA_42") (pintype "power_in"))
      (node (ref "U1") (pin "43") (pinfunction "VddA_43") (pintype "power_in"))
      (node (ref "U1") (pin "44") (pinfunction "VddA_44") (pintype "power_in"))
    )
    (net (code "58") (name "Net-(C6-Pad1)") (class "Default")
      (node (ref "C6") (pin "1") (pinfunction "1_1") (pintype "passive"))
      (node (ref "R10") (pin "1") (pinfunction "1_1") (pintype "passive"))
      (node (ref "R8") (pin "1") (pinfunction "1_1") (pintype "passive"))
    )
    (net (code "59") (name "Net-(C9-Pad1)") (class "Default")
      (node (ref "C9") (pin "1") (pinfunction "1_1") (pintype "passive"))
      (node (ref "R12") (pin "1") (pinfunction "1_1") (pintype "passive"))
      (node (ref "R14") (pin "1") (pinfunction "1_1") (pintype "passive"))
    )
    (net (code "60") (name "Net-(C10-Pad1)") (class "Default")
      (node (ref "C10") (pin "1") (pinfunction "1_1") (pintype "passive"))
      (node (ref "C11") (pin "1") (pinfunction "1_1") (pintype "passive"))
      (node (ref "L1") (pin "2") (pinfunction "2_2") (pintype "passive"))
      (node (ref "R1") (pin "1") (pinfunction "1_1") (pintype "passive"))
      (node (ref "R2") (pin "1") (pinfunction "1_1") (pintype "passive"))
      (node (ref "U2") (pin "5") (pinfunction "Vcc_5") (pintype "power_in"))
      (node (ref "U2") (pin "6") (pinfunction "Vcc_6") (pintype "power_in"))
      (node (ref "U2") (pin "7") (pinfunction "Vcc_7") (pintype "power_in"))
      (node (ref "U2") (pin "8") (pinfunction "Vcc_8") (pintype "power_in"))
    )
    (net (code "61") (name "Net-(C15-Pad1)") (class "Default")
      (node (ref "C15") (pin "1") (pinfunction "1_1") (pintype "passive"))
      (node (ref "R21") (pin "2") (pinfunction "2_2") (pintype "passive"))
      (node (ref "R22") (pin "2") (pinfunction "2_2") (pintype "passive"))
    )
    (net (code "62") (name "Net-(C16-Pad1)") (class "Default")
      (node (ref "C16") (pin "1") (pinfunction "1_1") (pintype "passive"))
      (node (ref "C17") (pin "1") (pinfunction "1_1") (pintype "passive"))
      (node (ref "L4") (pin "2") (pinfunction "2_2") (pintype "passive"))
      (node (ref "U3") (pin "29") (pinfunction "VddA_29") (pintype "power_in"))
      (node (ref "U3") (pin "32") (pinfunction "VddA_32") (pintype "power_in"))
      (node (ref "U3") (pin "33") (pinfunction "VddA_33") (pintype "power_in"))
      (node (ref "U3") (pin "36") (pinfunction "VddA_36") (pintype "power_in"))
      (node (ref "U3") (pin "38") (pinfunction "VddA_38") (pintype "power_in"))
      (node (ref "U3") (pin "41") (pinfunction "VddA_41") (pintype "power_in"))
      (node (ref "U3") (pin "42") (pinfunction "VddA_42") (pintype "power_in"))
      (node (ref "U3") (pin "43") (pinfunction "VddA_43") (pintype "power_in"))
      (node (ref "U3") (pin "44") (pinfunction "VddA_44") (pintype "power_in"))
    )
    (net (code "63") (name "Net-(C21-Pad1)") (class "Default")
      (node (ref "C21") (pin "1") (pinfunction "1_1") (pintype "passive"))
      (node (ref "R38") (pin "1") (pinfunction "1_1") (pintype "passive"))
      (node (ref "R40") (pin "1") (pinfunction "1_1") (pintype "passive"))
    )
    (net (code "64") (name "Net-(C24-Pad1)") (class "Default")
      (node (ref "C24") (pin "1") (pinfunction "1_1") (pintype "passive"))
      (node (ref "R42") (pin "1") (pinfunction "1_1") (pintype "passive"))
      (node (ref "R44") (pin "1") (pinfunction "1_1") (pintype "passive"))
    )
    (net (code "65") (name "Net-(C26-Pad1)") (class "Default")
      (node (ref "C26") (pin "1") (pinfunction "1_1") (pintype "passive"))
      (node (ref "C27") (pin "1") (pinfunction "1_1") (pintype "passive"))
      (node (ref "L3") (pin "2") (pinfunction "2_2") (pintype "passive"))
      (node (ref "R31") (pin "1") (pinfunction "1_1") (pintype "passive"))
      (node (ref "R32") (pin "1") (pinfunction "1_1") (pintype "passive"))
      (node (ref "U4") (pin "5") (pinfunction "Vcc_5") (pintype "power_in"))
      (node (ref "U4") (pin "6") (pinfunction "Vcc_6") (pintype "power_in"))
      (node (ref "U4") (pin "7") (pinfunction "Vcc_7") (pintype "power_in"))
      (node (ref "U4") (pin "8") (pinfunction "Vcc_8") (pintype "power_in"))
    )
    (net (code "66") (name "Net-(C30-Pad1)") (class "Default")
      (node (ref "C30") (pin "1") (pinfunction "1_1") (pintype "passive"))
      (node (ref "R51") (pin "2") (pinfunction "2_2") (pintype "passive"))
      (node (ref "R52") (pin "2") (pinfunction "2_2") (pintype "passive"))
    )
    (net (code "67") (name "Net-(U1-D0)") (class "Default")
      (node (ref "R3") (pin "1") (pinfunction "1_1") (pintype "passive"))
      (node (ref "U1") (pin "3") (pinfunction "D0_3") (pintype "output"))
    )
    (net (code "68") (name "Net-(U1-D1)") (class "Default")
      (node (ref "R4") (pin "1") (pinfunction "1_1") (pintype "passive"))
      (node (ref "U1") (pin "4") (pinfunction "D1_4") (pintype "output"))
    )
    (net (code "69") (name "Net-(U1-D2)") (class "Default")
      (node (ref "R5") (pin "1") (pinfunction "1_1") (pintype "passive"))
      (node (ref "U1") (pin "5") (pinfunction "D2_5") (pintype "output"))
    )
    (net (code "70") (name "Net-(U1-D3)") (class "Default")
      (node (ref "R6") (pin "1") (pinfunction "1_1") (pintype "passive"))
      (node (ref "U1") (pin "6") (pinfunction "D3_6") (pintype "output"))
    )
    (net (code "71") (name "Net-(U1-D4)") (class "Default")
      (node (ref "R9") (pin "1") (pinfunction "1_1") (pintype "passive"))
      (node (ref "U1") (pin "8") (pinfunction "D4_8") (pintype "output"))
    )
    (net (code "72") (name "Net-(U1-D5)") (class "Default")
      (node (ref "R11") (pin "1") (pinfunction "1_1") (pintype "passive"))
      (node (ref "U1") (pin "9") (pinfunction "D5_9") (pintype "output"))
    )
    (net (code "73") (name "Net-(U1-D6)") (class "Default")
      (node (ref "R13") (pin "1") (pinfunction "1_1") (pintype "passive"))
      (node (ref "U1") (pin "10") (pinfunction "D6_10") (pintype "output"))
    )
    (net (code "74") (name "Net-(U1-D7)") (class "Default")
      (node (ref "R15") (pin "1") (pinfunction "1_1") (pintype "passive"))
      (node (ref "U1") (pin "11") (pinfunction "D7_11") (pintype "output"))
    )
    (net (code "75") (name "Net-(U1-D8)") (class "Default")
      (node (ref "R16") (pin "1") (pinfunction "1_1") (pintype "passive"))
      (node (ref "U1") (pin "14") (pinfunction "D8_14") (pintype "output"))
    )
    (net (code "76") (name "Net-(U1-D9)") (class "Default")
      (node (ref "R17") (pin "1") (pinfunction "1_1") (pintype "passive"))
      (node (ref "U1") (pin "15") (pinfunction "D9_15") (pintype "output"))
    )
    (net (code "77") (name "Net-(U1-D10)") (class "Default")
      (node (ref "R18") (pin "1") (pinfunction "1_1") (pintype "passive"))
      (node (ref "U1") (pin "16") (pinfunction "D10_16") (pintype "output"))
    )
    (net (code "78") (name "Net-(U1-D11)") (class "Default")
      (node (ref "R23") (pin "1") (pinfunction "1_1") (pintype "passive"))
      (node (ref "U1") (pin "17") (pinfunction "D11_17") (pintype "output"))
    )
    (net (code "79") (name "Net-(U1-D12)") (class "Default")
      (node (ref "R24") (pin "1") (pinfunction "1_1") (pintype "passive"))
      (node (ref "U1") (pin "18") (pinfunction "D12_18") (pintype "output"))
    )
    (net (code "80") (name "Net-(U1-D13)") (class "Default")
      (node (ref "R25") (pin "1") (pinfunction "1_1") (pintype "passive"))
      (node (ref "U1") (pin "19") (pinfunction "D13_19") (pintype "output"))
    )
    (net (code "81") (name "Net-(U1-D14)") (class "Default")
      (node (ref "R26") (pin "1") (pinfunction "1_1") (pintype "passive"))
      (node (ref "U1") (pin "21") (pinfunction "D14_21") (pintype "output"))
    )
    (net (code "82") (name "Net-(U1-D15)") (class "Default")
      (node (ref "R28") (pin "1") (pinfunction "1_1") (pintype "passive"))
      (node (ref "U1") (pin "22") (pinfunction "D15_22") (pintype "output"))
    )
    (net (code "83") (name "Net-(U1-DCO)") (class "Default")
      (node (ref "R30") (pin "1") (pinfunction "1_1") (pintype "passive"))
      (node (ref "U1") (pin "2") (pinfunction "DCO_2") (pintype "power_in"))
    )
    (net (code "84") (name "Net-(U1-IN+)") (class "Default")
      (node (ref "C8") (pin "1") (pinfunction "1_1") (pintype "passive"))
      (node (ref "U1") (pin "40") (pinfunction "IN+_40") (pintype "input"))
    )
    (net (code "85") (name "Net-(U1-IN-)") (class "Default")
      (node (ref "C5") (pin "1") (pinfunction "1_1") (pintype "passive"))
      (node (ref "U1") (pin "39") (pinfunction "IN-_39") (pintype "input"))
    )
    (net (code "86") (name "Net-(U1-OR)") (class "Default")
      (node (ref "R29") (pin "1") (pinfunction "1_1") (pintype "passive"))
      (node (ref "U1") (pin "23") (pinfunction "OR_23") (pintype "power_in"))
    )
    (net (code "87") (name "Net-(U1-RBIAS)") (class "Default")
      (node (ref "R27") (pin "1") (pinfunction "1_1") (pintype "passive"))
      (node (ref "U1") (pin "30") (pinfunction "RBIAS_30") (pintype "passive"))
    )
    (net (code "88") (name "Net-(U1-VREF)") (class "Default")
      (node (ref "C13") (pin "1") (pinfunction "1_1") (pintype "passive"))
      (node (ref "C14") (pin "1") (pinfunction "1_1") (pintype "passive"))
      (node (ref "U1") (pin "28") (pinfunction "VREF_28") (pintype "passive"))
    )
    (net (code "89") (name "Net-(U2-en)") (class "Default")
      (node (ref "R1") (pin "2") (pinfunction "2_2") (pintype "passive"))
      (node (ref "R19") (pin "1") (pinfunction "1_1") (pintype "passive"))
      (node (ref "U2") (pin "12") (pinfunction "en_12") (pintype "passive"))
    )
    (net (code "90") (name "Net-(U2-vcom)") (class "Default")
      (node (ref "C12") (pin "1") (pinfunction "1_1") (pintype "passive"))
      (node (ref "R2") (pin "2") (pinfunction "2_2") (pintype "passive"))
      (node (ref "R20") (pin "1") (pinfunction "1_1") (pintype "passive"))
      (node (ref "U2") (pin "10") (pinfunction "vcom_10") (pintype "passive"))
    )
    (net (code "91") (name "Net-(U2-vin1)") (class "Default")
      (node (ref "R12") (pin "2") (pinfunction "2_2") (pintype "passive"))
      (node (ref "U2") (pin "3") (pinfunction "vin1_3") (pintype "passive"))
    )
    (net (code "92") (name "Net-(U2-vin2)") (class "Default")
      (node (ref "R14") (pin "2") (pinfunction "2_2") (pintype "passive"))
      (node (ref "U2") (pin "4") (pinfunction "vin2_4") (pintype "passive"))
    )
    (net (code "93") (name "Net-(U2-vip1)") (class "Default")
      (node (ref "R10") (pin "2") (pinfunction "2_2") (pintype "passive"))
      (node (ref "U2") (pin "2") (pinfunction "vip1_2") (pintype "passive"))
    )
    (net (code "94") (name "Net-(U2-vip2)") (class "Default")
      (node (ref "R8") (pin "2") (pinfunction "2_2") (pintype "passive"))
      (node (ref "U2") (pin "1") (pinfunction "vip2_1") (pintype "passive"))
    )
    (net (code "95") (name "Net-(U2-von)") (class "Default")
      (node (ref "C5") (pin "2") (pinfunction "2_2") (pintype "passive"))
      (node (ref "C7") (pin "1") (pinfunction "1_1") (pintype "passive"))
      (node (ref "R21") (pin "1") (pinfunction "1_1") (pintype "passive"))
      (node (ref "U2") (pin "11") (pinfunction "von_11") (pintype "passive"))
    )
    (net (code "96") (name "Net-(U2-vop)") (class "Default")
      (node (ref "C7") (pin "2") (pinfunction "2_2") (pintype "passive"))
      (node (ref "C8") (pin "2") (pinfunction "2_2") (pintype "passive"))
      (node (ref "R22") (pin "1") (pinfunction "1_1") (pintype "passive"))
      (node (ref "U2") (pin "9") (pinfunction "vop_9") (pintype "passive"))
    )
    (net (code "97") (name "Net-(U3-D0)") (class "Default")
      (node (ref "R33") (pin "1") (pinfunction "1_1") (pintype "passive"))
      (node (ref "U3") (pin "3") (pinfunction "D0_3") (pintype "output"))
    )
    (net (code "98") (name "Net-(U3-D1)") (class "Default")
      (node (ref "R34") (pin "1") (pinfunction "1_1") (pintype "passive"))
      (node (ref "U3") (pin "4") (pinfunction "D1_4") (pintype "output"))
    )
    (net (code "99") (name "Net-(U3-D2)") (class "Default")
      (node (ref "R35") (pin "1") (pinfunction "1_1") (pintype "passive"))
      (node (ref "U3") (pin "5") (pinfunction "D2_5") (pintype "output"))
    )
    (net (code "100") (name "Net-(U3-D3)") (class "Default")
      (node (ref "R36") (pin "1") (pinfunction "1_1") (pintype "passive"))
      (node (ref "U3") (pin "6") (pinfunction "D3_6") (pintype "output"))
    )
    (net (code "101") (name "Net-(U3-D4)") (class "Default")
      (node (ref "R39") (pin "1") (pinfunction "1_1") (pintype "passive"))
      (node (ref "U3") (pin "8") (pinfunction "D4_8") (pintype "output"))
    )
    (net (code "102") (name "Net-(U3-D5)") (class "Default")
      (node (ref "R41") (pin "1") (pinfunction "1_1") (pintype "passive"))
      (node (ref "U3") (pin "9") (pinfunction "D5_9") (pintype "output"))
    )
    (net (code "103") (name "Net-(U3-D6)") (class "Default")
      (node (ref "R43") (pin "1") (pinfunction "1_1") (pintype "passive"))
      (node (ref "U3") (pin "10") (pinfunction "D6_10") (pintype "output"))
    )
    (net (code "104") (name "Net-(U3-D7)") (class "Default")
      (node (ref "R45") (pin "1") (pinfunction "1_1") (pintype "passive"))
      (node (ref "U3") (pin "11") (pinfunction "D7_11") (pintype "output"))
    )
    (net (code "105") (name "Net-(U3-D8)") (class "Default")
      (node (ref "R46") (pin "1") (pinfunction "1_1") (pintype "passive"))
      (node (ref "U3") (pin "14") (pinfunction "D8_14") (pintype "output"))
    )
    (net (code "106") (name "Net-(U3-D9)") (class "Default")
      (node (ref "R47") (pin "1") (pinfunction "1_1") (pintype "passive"))
      (node (ref "U3") (pin "15") (pinfunction "D9_15") (pintype "output"))
    )
    (net (code "107") (name "Net-(U3-D10)") (class "Default")
      (node (ref "R48") (pin "1") (pinfunction "1_1") (pintype "passive"))
      (node (ref "U3") (pin "16") (pinfunction "D10_16") (pintype "output"))
    )
    (net (code "108") (name "Net-(U3-D11)") (class "Default")
      (node (ref "R53") (pin "1") (pinfunction "1_1") (pintype "passive"))
      (node (ref "U3") (pin "17") (pinfunction "D11_17") (pintype "output"))
    )
    (net (code "109") (name "Net-(U3-D12)") (class "Default")
      (node (ref "R54") (pin "1") (pinfunction "1_1") (pintype "passive"))
      (node (ref "U3") (pin "18") (pinfunction "D12_18") (pintype "output"))
    )
    (net (code "110") (name "Net-(U3-D13)") (class "Default")
      (node (ref "R55") (pin "1") (pinfunction "1_1") (pintype "passive"))
      (node (ref "U3") (pin "19") (pinfunction "D13_19") (pintype "output"))
    )
    (net (code "111") (name "Net-(U3-D14)") (class "Default")
      (node (ref "R56") (pin "1") (pinfunction "1_1") (pintype "passive"))
      (node (ref "U3") (pin "21") (pinfunction "D14_21") (pintype "output"))
    )
    (net (code "112") (name "Net-(U3-D15)") (class "Default")
      (node (ref "R58") (pin "1") (pinfunction "1_1") (pintype "passive"))
      (node (ref "U3") (pin "22") (pinfunction "D15_22") (pintype "output"))
    )
    (net (code "113") (name "Net-(U3-DCO)") (class "Default")
      (node (ref "R60") (pin "1") (pinfunction "1_1") (pintype "passive"))
      (node (ref "U3") (pin "2") (pinfunction "DCO_2") (pintype "power_in"))
    )
    (net (code "114") (name "Net-(U3-IN+)") (class "Default")
      (node (ref "C23") (pin "1") (pinfunction "1_1") (pintype "passive"))
      (node (ref "U3") (pin "40") (pinfunction "IN+_40") (pintype "input"))
    )
    (net (code "115") (name "Net-(U3-IN-)") (class "Default")
      (node (ref "C20") (pin "1") (pinfunction "1_1") (pintype "passive"))
      (node (ref "U3") (pin "39") (pinfunction "IN-_39") (pintype "input"))
    )
    (net (code "116") (name "Net-(U3-OR)") (class "Default")
      (node (ref "R59") (pin "1") (pinfunction "1_1") (pintype "passive"))
      (node (ref "U3") (pin "23") (pinfunction "OR_23") (pintype "power_in"))
    )
    (net (code "117") (name "Net-(U3-RBIAS)") (class "Default")
      (node (ref "R57") (pin "1") (pinfunction "1_1") (pintype "passive"))
      (node (ref "U3") (pin "30") (pinfunction "RBIAS_30") (pintype "passive"))
    )
    (net (code "118") (name "Net-(U3-VREF)") (class "Default")
      (node (ref "C28") (pin "1") (pinfunction "1_1") (pintype "passive"))
      (node (ref "C29") (pin "1") (pinfunction "1_1") (pintype "passive"))
      (node (ref "U3") (pin "28") (pinfunction "VREF_28") (pintype "passive"))
    )
    (net (code "119") (name "Net-(U4-en)") (class "Default")
      (node (ref "R31") (pin "2") (pinfunction "2_2") (pintype "passive"))
      (node (ref "R49") (pin "1") (pinfunction "1_1") (pintype "passive"))
      (node (ref "U4") (pin "12") (pinfunction "en_12") (pintype "passive"))
    )
    (net (code "120") (name "Net-(U4-vcom)") (class "Default")
      (node (ref "C25") (pin "1") (pinfunction "1_1") (pintype "passive"))
      (node (ref "R32") (pin "2") (pinfunction "2_2") (pintype "passive"))
      (node (ref "R50") (pin "1") (pinfunction "1_1") (pintype "passive"))
      (node (ref "U4") (pin "10") (pinfunction "vcom_10") (pintype "passive"))
    )
    (net (code "121") (name "Net-(U4-vin1)") (class "Default")
      (node (ref "R42") (pin "2") (pinfunction "2_2") (pintype "passive"))
      (node (ref "U4") (pin "3") (pinfunction "vin1_3") (pintype "passive"))
    )
    (net (code "122") (name "Net-(U4-vin2)") (class "Default")
      (node (ref "R44") (pin "2") (pinfunction "2_2") (pintype "passive"))
      (node (ref "U4") (pin "4") (pinfunction "vin2_4") (pintype "passive"))
    )
    (net (code "123") (name "Net-(U4-vip1)") (class "Default")
      (node (ref "R40") (pin "2") (pinfunction "2_2") (pintype "passive"))
      (node (ref "U4") (pin "2") (pinfunction "vip1_2") (pintype "passive"))
    )
    (net (code "124") (name "Net-(U4-vip2)") (class "Default")
      (node (ref "R38") (pin "2") (pinfunction "2_2") (pintype "passive"))
      (node (ref "U4") (pin "1") (pinfunction "vip2_1") (pintype "passive"))
    )
    (net (code "125") (name "Net-(U4-von)") (class "Default")
      (node (ref "C20") (pin "2") (pinfunction "2_2") (pintype "passive"))
      (node (ref "C22") (pin "1") (pinfunction "1_1") (pintype "passive"))
      (node (ref "R51") (pin "1") (pinfunction "1_1") (pintype "passive"))
      (node (ref "U4") (pin "11") (pinfunction "von_11") (pintype "passive"))
    )
    (net (code "126") (name "Net-(U4-vop)") (class "Default")
      (node (ref "C22") (pin "2") (pinfunction "2_2") (pintype "passive"))
      (node (ref "C23") (pin "2") (pinfunction "2_2") (pintype "passive"))
      (node (ref "R52") (pin "1") (pinfunction "1_1") (pintype "passive"))
      (node (ref "U4") (pin "9") (pinfunction "vop_9") (pintype "passive"))
    )
    (net (code "127") (name "unconnected-(U1-VCM-Pad37)") (class "Default")
      (node (ref "U1") (pin "37") (pinfunction "VCM_37") (pintype "passive"))
    )
    (net (code "128") (name "unconnected-(U1-VREFn-Pad26)") (class "Default")
      (node (ref "U1") (pin "26") (pinfunction "VREFn_26") (pintype "passive"))
    )
    (net (code "129") (name "unconnected-(U1-VREFp-Pad27)") (class "Default")
      (node (ref "U1") (pin "27") (pinfunction "VREFp_27") (pintype "passive"))
    )
    (net (code "130") (name "unconnected-(U3-VCM-Pad37)") (class "Default")
      (node (ref "U3") (pin "37") (pinfunction "VCM_37") (pintype "passive"))
    )
    (net (code "131") (name "unconnected-(U3-VREFn-Pad26)") (class "Default")
      (node (ref "U3") (pin "26") (pinfunction "VREFn_26") (pintype "passive"))
    )
    (net (code "132") (name "unconnected-(U3-VREFp-Pad27)") (class "Default")
      (node (ref "U3") (pin "27") (pinfunction "VREFp_27") (pintype "passive"))
    )
  )
)
